# PowerMeterV2.net
KiCad netlist of a schematic drawn in Altium Designer
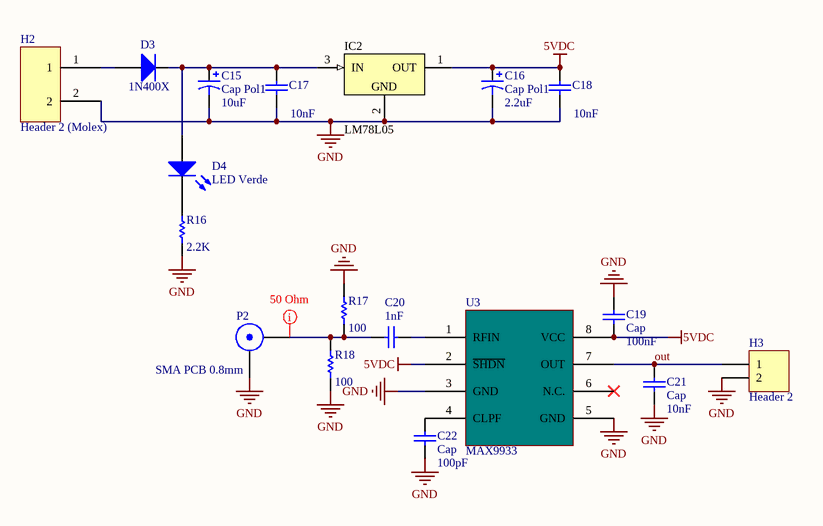
[diagram p0: PowerMeterV2.SchDoc]

(export (version "E")
  (design (tool "Eeschema 10.0.6"))
  (components
    (comp (ref "C15")
      (value "Cap Pol1")
      (footprint "CAPPR2-5x11")
      (description "Polarized Capacitor (Radial)")
      (fields (field (name "ALTIUM_VALUE") "10uF") (field (name "PUBLISHER") "Altium Limited"))
      (libsource (lib "Miscellaneous Devices") (part "Cap Pol1"))
    )
    (comp (ref "C16")
      (value "Cap Pol1")
      (footprint "CAPPR2-5x11")
      (description "Polarized Capacitor (Radial)")
      (fields (field (name "ALTIUM_VALUE") "2.2uF") (field (name "PUBLISHER") "Altium Limited"))
      (libsource (lib "Miscellaneous Devices") (part "Cap Pol1"))
    )
    (comp (ref "C17")
      (value "10nF")
      (footprint "6-0805_L")
      (description "Capacitor")
      (fields (field (name "PUBLISHER") "Altium Limited"))
      (libsource (lib "Miscellaneous Devices") (part "Cap"))
    )
    (comp (ref "C18")
      (value "10nF")
      (footprint "6-0805_L")
      (description "Capacitor")
      (fields (field (name "PUBLISHER") "Altium Limited"))
      (libsource (lib "Miscellaneous Devices") (part "Cap"))
    )
    (comp (ref "C19")
      (value "Cap")
      (footprint "Miscellaneous Devices:6-0805_L")
      (description "Capacitor")
      (fields (field (name "ALTIUM_VALUE") "100nF") (field (name "PUBLISHER") "Altium Limited"))
      (libsource (lib "Miscellaneous Devices") (part "Cap"))
    )
    (comp (ref "C20")
      (value "1nF")
      (footprint "Miscellaneous Devices:6-0805_L")
      (description "Capacitor")
      (fields (field (name "PUBLISHER") "Altium Limited"))
      (libsource (lib "Miscellaneous Devices") (part "Cap"))
    )
    (comp (ref "C21")
      (value "Cap")
      (footprint "Miscellaneous Devices:6-0805_L")
      (description "Capacitor")
      (fields (field (name "ALTIUM_VALUE") "10nF") (field (name "PUBLISHER") "Altium Limited"))
      (libsource (lib "Miscellaneous Devices") (part "Cap"))
    )
    (comp (ref "C22")
      (value "Cap")
      (footprint "Miscellaneous Devices:6-0805_L")
      (description "Capacitor")
      (fields (field (name "ALTIUM_VALUE") "100pF") (field (name "PUBLISHER") "Altium Limited"))
      (libsource (lib "Miscellaneous Devices") (part "Cap"))
    )
    (comp (ref "D3")
      (value "1N400X")
      (footprint "MELF")
      (description "Default Diode")
      (fields (field (name "PUBLISHER") "Altium Limited"))
      (libsource (lib "Miscellaneous Devices") (part "Diode"))
    )
    (comp (ref "D4")
      (value "LED Verde")
      (footprint "Componentes:LED")
      (description "Typical INFRARED GaAs LED")
      (fields (field (name "PUBLISHER") "Altium Limited"))
      (libsource (lib "Componentes") (part "LED0"))
    )
    (comp (ref "H2")
      (value "Header 2 (Molex)")
      (footprint "Header 2 (Molex)")
      (description "2-Pin Header with Lock (0_100in pitch)")
      (libsource (lib "ComponentesPropios") (part "Header 2 (Molex)"))
    )
    (comp (ref "H3")
      (value "Header 2")
      (footprint "HDR1X2")
      (description "Header, 2-Pin")
      (fields (field (name "PUBLISHER") "Altium Limited"))
      (libsource (lib "Miscellaneous Connectors") (part "Header 2"))
    )
    (comp (ref "IC2")
      (value "78Lxx")
      (footprint "TO-92 (2)")
      (description "Regulador fijo de tensión positiva 100mA")
      (fields (field (name "NOMBRE") "LM78L05"))
      (libsource (lib "ComponentesPropios") (part "78Lxx"))
    )
    (comp (ref "P2")
      (value "SMA PCB 0.8mm")
      (footprint "PCB librería:SMA PCB 0.8mm")
      (libsource (lib "Esquematicos librería") (part "SMA PCB 0.8mm"))
    )
    (comp (ref "R16")
      (value "2.2K")
      (footprint "6-0805_L")
      (description "Resistor")
      (fields (field (name "PUBLISHER") "Altium Limited"))
      (libsource (lib "Miscellaneous Devices") (part "Res1"))
    )
    (comp (ref "R17")
      (value "100")
      (footprint "6-0805_L")
      (description "Resistor")
      (fields (field (name "PUBLISHER") "Altium Limited"))
      (libsource (lib "Miscellaneous Devices") (part "Res1"))
    )
    (comp (ref "R18")
      (value "100")
      (footprint "6-0805_L")
      (description "Resistor")
      (fields (field (name "PUBLISHER") "Altium Limited"))
      (libsource (lib "Miscellaneous Devices") (part "Res1"))
    )
    (comp (ref "U3")
      (value "MAX9933")
      (footprint "8L uMAX")
      (description "RF LOG DETECTOR")
      (libsource (lib "ComponentesPropios") (part "MAX9933"))
    )
  )
  (nets
    (net (code "1") (name "/out") (class "Default")
      (node (ref "C21") (pin "1") (pinfunction "1_1") (pintype "passive"))
      (node (ref "H3") (pin "1") (pinfunction "1_1") (pintype "passive"))
      (node (ref "U3") (pin "7") (pinfunction "OUT_7") (pintype "passive"))
    )
    (net (code "2") (name "5VDC") (class "Default")
      (node (ref "C16") (pin "1") (pinfunction "1_1") (pintype "passive"))
      (node (ref "C18") (pin "2") (pinfunction "2_2") (pintype "passive"))
      (node (ref "C19") (pin "2") (pinfunction "2_2") (pintype "passive"))
      (node (ref "IC2") (pin "1") (pinfunction "OUT_1") (pintype "power_in"))
      (node (ref "U3") (pin "2") (pinfunction "SHDN_2") (pintype "passive"))
      (node (ref "U3") (pin "8") (pinfunction "VCC_8") (pintype "passive"))
    )
    (net (code "3") (name "GND") (class "Default")
      (node (ref "C15") (pin "2") (pinfunction "2_2") (pintype "passive"))
      (node (ref "C16") (pin "2") (pinfunction "2_2") (pintype "passive"))
      (node (ref "C17") (pin "1") (pinfunction "1_1") (pintype "passive"))
      (node (ref "C18") (pin "1") (pinfunction "1_1") (pintype "passive"))
      (node (ref "C19") (pin "1") (pinfunction "1_1") (pintype "passive"))
      (node (ref "C21") (pin "2") (pinfunction "2_2") (pintype "passive"))
      (node (ref "C22") (pin "2") (pinfunction "2_2") (pintype "passive"))
      (node (ref "H2") (pin "2") (pinfunction "2_2") (pintype "passive"))
      (node (ref "H3") (pin "2") (pinfunction "2_2") (pintype "passive"))
      (node (ref "IC2") (pin "2") (pinfunction "GND_2") (pintype "power_in"))
      (node (ref "P2") (pin "2") (pinfunction "Y_2") (pintype "passive"))
      (node (ref "R16") (pin "1") (pinfunction "1_1") (pintype "passive"))
      (node (ref "R17") (pin "2") (pinfunction "2_2") (pintype "passive"))
      (node (ref "R18") (pin "1") (pinfunction "1_1") (pintype "passive"))
      (node (ref "U3") (pin "3") (pinfunction "GND_3") (pintype "passive"))
      (node (ref "U3") (pin "5") (pinfunction "GND_5") (pintype "passive"))
    )
    (net (code "4") (name "Net-(D3-A)") (class "Default")
      (node (ref "D3") (pin "1") (pinfunction "A_1") (pintype "passive"))
      (node (ref "H2") (pin "1") (pinfunction "1_1") (pintype "passive"))
    )
    (net (code "5") (name "Net-(D3-K)") (class "Default")
      (node (ref "C15") (pin "1") (pinfunction "1_1") (pintype "passive"))
      (node (ref "C17") (pin "2") (pinfunction "2_2") (pintype "passive"))
      (node (ref "D3") (pin "2") (pinfunction "K_2") (pintype "passive"))
      (node (ref "D4") (pin "1") (pinfunction "A_1") (pintype "passive"))
      (node (ref "IC2") (pin "3") (pinfunction "IN_3") (pintype "input"))
    )
    (net (code "6") (name "Net-(D4-K)") (class "Default")
      (node (ref "D4") (pin "2") (pinfunction "K_2") (pintype "passive"))
      (node (ref "R16") (pin "2") (pinfunction "2_2") (pintype "passive"))
    )
    (net (code "7") (name "Net-(P2-X)") (class "Default")
      (node (ref "C20") (pin "1") (pinfunction "1_1") (pintype "passive"))
      (node (ref "P2") (pin "1") (pinfunction "X_1") (pintype "passive"))
      (node (ref "R17") (pin "1") (pinfunction "1_1") (pintype "passive"))
      (node (ref "R18") (pin "2") (pinfunction "2_2") (pintype "passive"))
    )
    (net (code "8") (name "Net-(U3-CLPF)") (class "Default")
      (node (ref "C22") (pin "1") (pinfunction "1_1") (pintype "passive"))
      (node (ref "U3") (pin "4") (pinfunction "CLPF_4") (pintype "passive"))
    )
    (net (code "9") (name "Net-(U3-RFIN)") (class "Default")
      (node (ref "C20") (pin "2") (pinfunction "2_2") (pintype "passive"))
      (node (ref "U3") (pin "1") (pinfunction "RFIN_1") (pintype "passive"))
    )
    (net (code "10") (name "unconnected-(U3-N.C.-Pad6)") (class "Default")
      (node (ref "U3") (pin "6") (pinfunction "N.C._6") (pintype "passive+no_connect"))
    )
  )
)
